# Bias_Regulators_1.net
KiCad netlist of a schematic drawn in Altium Designer
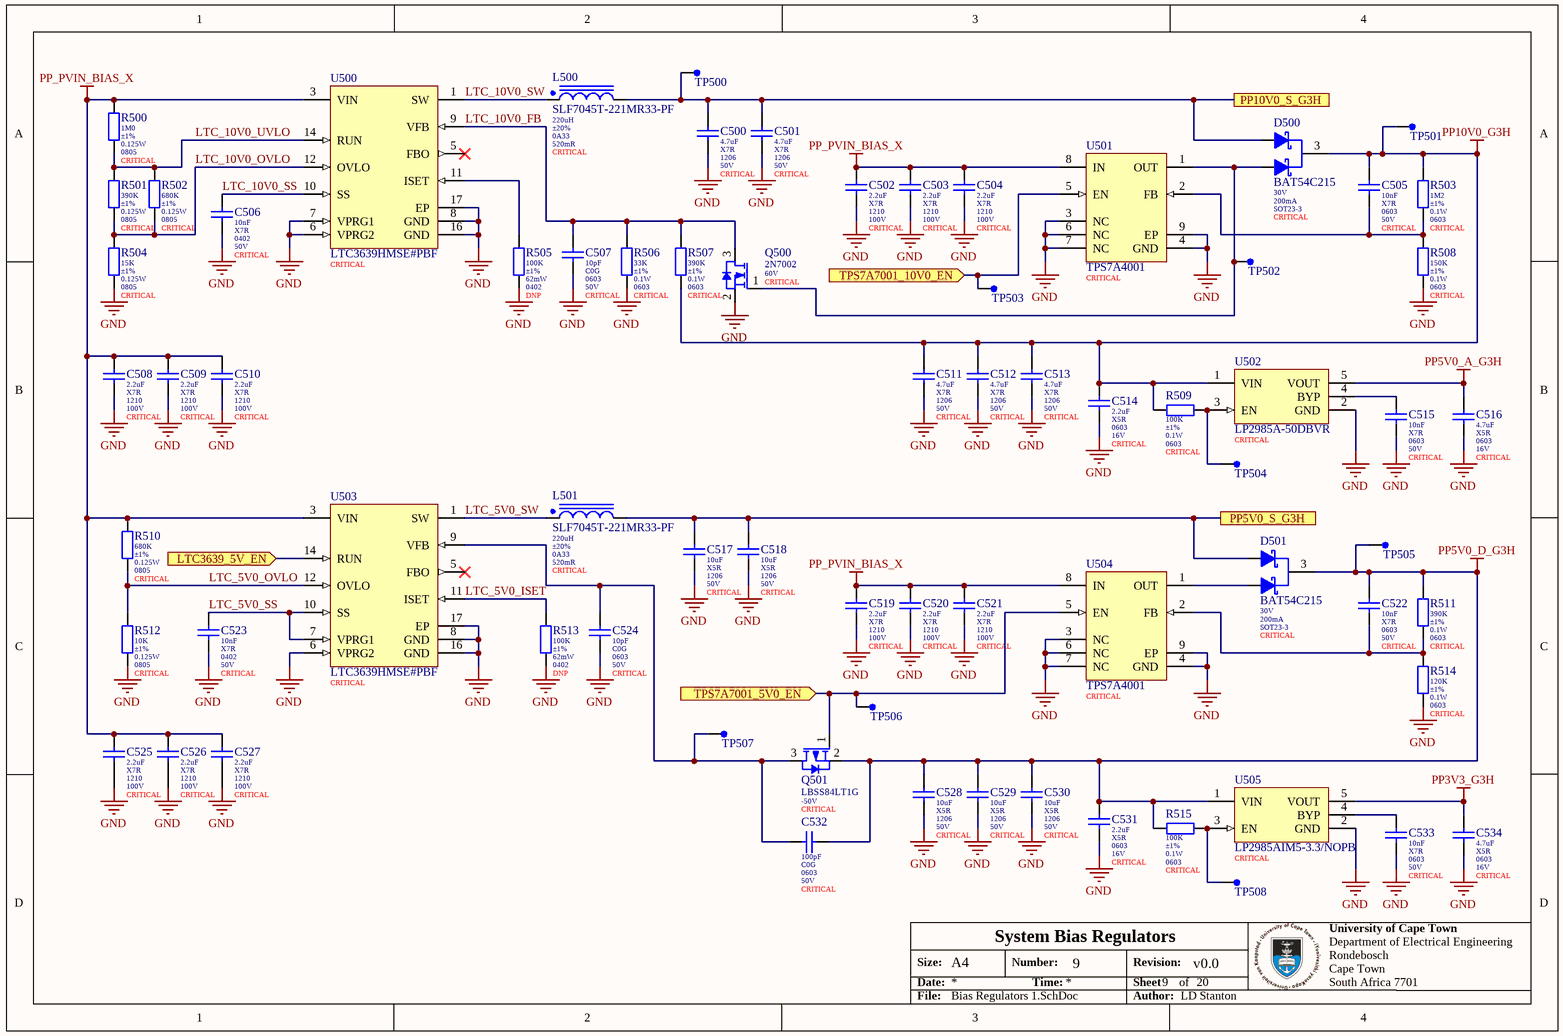
[diagram p0: Bias Regulators 1.SchDoc]

(export (version "E")
  (design (tool "Eeschema 10.0.6"))
  (components
    (comp (ref "C500")
      (value "4.7uF")
      (footprint "1206_125 (Guandong) B")
      (description "MLCC 4.7uF 1206 50V X7R ±10%")
      (fields
        (field (name "DIELECTRIC") "X7R")
        (field (name "PACKAGE") "1206")
        (field (name "VOLTAGE") "50V")
        (field (name "POPULATE") "CRITICAL")
        (field (name "TOLERANCE") "±15%")
        (field (name "MANUFACTURER") "Guandong")
      )
      (libsource (lib "University of Cape Town") (part "Symbol"))
    )
    (comp (ref "C501")
      (value "4.7uF")
      (footprint "1206_125 (Guandong) B")
      (description "MLCC 4.7uF 1206 50V X7R ±10%")
      (fields
        (field (name "DIELECTRIC") "X7R")
        (field (name "PACKAGE") "1206")
        (field (name "VOLTAGE") "50V")
        (field (name "POPULATE") "CRITICAL")
        (field (name "TOLERANCE") "±15%")
        (field (name "MANUFACTURER") "Guandong")
      )
      (libsource (lib "University of Cape Town") (part "Symbol"))
    )
    (comp (ref "C502")
      (value "2.2uF")
      (footprint "1212_250_J (Samsumg) B")
      (description "MLCC 2.2uF 1210 100V X7R ±10%")
      (fields
        (field (name "DIELECTRIC") "X7R")
        (field (name "PACKAGE") "1210")
        (field (name "VOLTAGE") "100V")
        (field (name "POPULATE") "CRITICAL")
        (field (name "LCSC PART NUMBER") "C55151")
        (field (name "TOLERANCE") "±10%")
      )
      (libsource (lib "University of Cape Town") (part "Symbol"))
    )
    (comp (ref "C503")
      (value "2.2uF")
      (footprint "1212_250_J (Samsumg) B")
      (description "MLCC 2.2uF 1210 100V X7R ±10%")
      (fields
        (field (name "DIELECTRIC") "X7R")
        (field (name "PACKAGE") "1210")
        (field (name "VOLTAGE") "100V")
        (field (name "POPULATE") "CRITICAL")
        (field (name "LCSC PART NUMBER") "C55151")
        (field (name "TOLERANCE") "±10%")
      )
      (libsource (lib "University of Cape Town") (part "Symbol"))
    )
    (comp (ref "C504")
      (value "2.2uF")
      (footprint "1212_250_J (Samsumg) B")
      (description "MLCC 2.2uF 1210 100V X7R ±10%")
      (fields
        (field (name "DIELECTRIC") "X7R")
        (field (name "PACKAGE") "1210")
        (field (name "VOLTAGE") "100V")
        (field (name "POPULATE") "CRITICAL")
        (field (name "LCSC PART NUMBER") "C55151")
        (field (name "TOLERANCE") "±10%")
      )
      (libsource (lib "University of Cape Town") (part "Symbol"))
    )
    (comp (ref "C505")
      (value "10nF")
      (footprint "0603_080 (Guandong) B")
      (description "MLCC 10nF 0603 50V X7R ±10%")
      (fields
        (field (name "DIELECTRIC") "X7R")
        (field (name "PACKAGE") "0603")
        (field (name "VOLTAGE") "50V")
        (field (name "POPULATE") "CRITICAL")
        (field (name "LCSC PART NUMBER") "C57112")
        (field (name "MANUFACTURER") "Guandong")
      )
      (libsource (lib "University of Cape Town") (part "Symbol"))
    )
    (comp (ref "C506")
      (value "10nF")
      (footprint "0402_050_5 (Samsumg) B")
      (description "MLCC 10nF 0402 50V X7R ±10%")
      (fields
        (field (name "DIELECTRIC") "X7R")
        (field (name "PACKAGE") "0402")
        (field (name "VOLTAGE") "50V")
        (field (name "POPULATE") "CRITICAL")
        (field (name "TOLERANCE") "±10%")
        (field (name "LCSC PART NUMBER") "C15195")
      )
      (libsource (lib "University of Cape Town") (part "Symbol"))
    )
    (comp (ref "C507")
      (value "10pF")
      (footprint "0603_080_8 (Samsung) B")
      (description "MLCC 10pF 0603 C0G ±0.1pF")
      (fields
        (field (name "DIELECTRIC") "C0G")
        (field (name "PACKAGE") "0603")
        (field (name "VOLTAGE") "50V")
        (field (name "POPULATE") "CRITICAL")
        (field (name "TOLERANCE") "±0.1pF")
        (field (name "LCSC PART NUMBER") "C1634")
      )
      (libsource (lib "University of Cape Town") (part "Symbol"))
    )
    (comp (ref "C508")
      (value "2.2uF")
      (footprint "1212_250_J (Samsumg) B")
      (description "MLCC 2.2uF 1210 100V X7R ±10%")
      (fields
        (field (name "DIELECTRIC") "X7R")
        (field (name "PACKAGE") "1210")
        (field (name "VOLTAGE") "100V")
        (field (name "POPULATE") "CRITICAL")
        (field (name "LCSC PART NUMBER") "C55151")
        (field (name "TOLERANCE") "±10%")
      )
      (libsource (lib "University of Cape Town") (part "Symbol"))
    )
    (comp (ref "C509")
      (value "2.2uF")
      (footprint "1212_250_J (Samsumg) B")
      (description "MLCC 2.2uF 1210 100V X7R ±10%")
      (fields
        (field (name "DIELECTRIC") "X7R")
        (field (name "PACKAGE") "1210")
        (field (name "VOLTAGE") "100V")
        (field (name "POPULATE") "CRITICAL")
        (field (name "LCSC PART NUMBER") "C55151")
        (field (name "TOLERANCE") "±10%")
      )
      (libsource (lib "University of Cape Town") (part "Symbol"))
    )
    (comp (ref "C510")
      (value "2.2uF")
      (footprint "1212_250_J (Samsumg) B")
      (description "MLCC 2.2uF 1210 100V X7R ±10%")
      (fields
        (field (name "DIELECTRIC") "X7R")
        (field (name "PACKAGE") "1210")
        (field (name "VOLTAGE") "100V")
        (field (name "POPULATE") "CRITICAL")
        (field (name "LCSC PART NUMBER") "C55151")
        (field (name "TOLERANCE") "±10%")
      )
      (libsource (lib "University of Cape Town") (part "Symbol"))
    )
    (comp (ref "C511")
      (value "4.7uF")
      (footprint "1206_125 (Guandong) B")
      (description "MLCC 4.7uF 1206 50V X7R ±10%")
      (fields
        (field (name "DIELECTRIC") "X7R")
        (field (name "PACKAGE") "1206")
        (field (name "VOLTAGE") "50V")
        (field (name "POPULATE") "CRITICAL")
        (field (name "TOLERANCE") "±15%")
        (field (name "MANUFACTURER") "Guandong")
      )
      (libsource (lib "University of Cape Town") (part "Symbol"))
    )
    (comp (ref "C512")
      (value "4.7uF")
      (footprint "1206_125 (Guandong) B")
      (description "MLCC 4.7uF 1206 50V X7R ±10%")
      (fields
        (field (name "DIELECTRIC") "X7R")
        (field (name "PACKAGE") "1206")
        (field (name "VOLTAGE") "50V")
        (field (name "POPULATE") "CRITICAL")
        (field (name "TOLERANCE") "±15%")
        (field (name "MANUFACTURER") "Guandong")
      )
      (libsource (lib "University of Cape Town") (part "Symbol"))
    )
    (comp (ref "C513")
      (value "4.7uF")
      (footprint "1206_125 (Guandong) B")
      (description "MLCC 4.7uF 1206 50V X7R ±10%")
      (fields
        (field (name "DIELECTRIC") "X7R")
        (field (name "PACKAGE") "1206")
        (field (name "VOLTAGE") "50V")
        (field (name "POPULATE") "CRITICAL")
        (field (name "TOLERANCE") "±15%")
        (field (name "MANUFACTURER") "Guandong")
      )
      (libsource (lib "University of Cape Town") (part "Symbol"))
    )
    (comp (ref "C514")
      (value "2.2uF")
      (footprint "0603_080_8 (Samsung) B")
      (description "MLCC 2.2uF 0603 16V X5R ±10%")
      (fields
        (field (name "DIELECTRIC") "X5R")
        (field (name "PACKAGE") "0603")
        (field (name "VOLTAGE") "16V")
        (field (name "POPULATE") "CRITICAL")
        (field (name "TOLERANCE") "±10%")
        (field (name "LCSC PART NUMBER") "C23630")
      )
      (libsource (lib "University of Cape Town") (part "Symbol"))
    )
    (comp (ref "C515")
      (value "10nF")
      (footprint "0603_080 (Guandong) B")
      (description "MLCC 10nF 0603 50V X7R ±10%")
      (fields
        (field (name "DIELECTRIC") "X7R")
        (field (name "PACKAGE") "0603")
        (field (name "VOLTAGE") "50V")
        (field (name "POPULATE") "CRITICAL")
        (field (name "LCSC PART NUMBER") "C57112")
        (field (name "MANUFACTURER") "Guandong")
      )
      (libsource (lib "University of Cape Town") (part "Symbol"))
    )
    (comp (ref "C516")
      (value "4.7uF")
      (footprint "0603_080_8 (Samsung) B")
      (description "MLCC 4.7uF 0603 16V X5R ±10%")
      (fields
        (field (name "DIELECTRIC") "X5R")
        (field (name "PACKAGE") "0603")
        (field (name "VOLTAGE") "16V")
        (field (name "POPULATE") "CRITICAL")
        (field (name "LCSC PART NUMBER") "C19666")
        (field (name "TOLERANCE") "±10%")
      )
      (libsource (lib "University of Cape Town") (part "Symbol"))
    )
    (comp (ref "C517")
      (value "10uF")
      (footprint "1206_160_H (Samsumg) B")
      (description "MLCC 10uF 1206 50V X5R ±10%")
      (fields
        (field (name "DIELECTRIC") "X5R")
        (field (name "PACKAGE") "1206")
        (field (name "VOLTAGE") "50V")
        (field (name "POPULATE") "CRITICAL")
        (field (name "LCSC PART NUMBER") "C13585")
        (field (name "MANUFACTURER") "Samsung")
      )
      (libsource (lib "University of Cape Town") (part "Symbol"))
    )
    (comp (ref "C518")
      (value "10uF")
      (footprint "1206_160_H (Samsumg) B")
      (description "MLCC 10uF 1206 50V X5R ±10%")
      (fields
        (field (name "DIELECTRIC") "X5R")
        (field (name "PACKAGE") "1206")
        (field (name "VOLTAGE") "50V")
        (field (name "POPULATE") "CRITICAL")
        (field (name "LCSC PART NUMBER") "C13585")
        (field (name "MANUFACTURER") "Samsung")
      )
      (libsource (lib "University of Cape Town") (part "Symbol"))
    )
    (comp (ref "C519")
      (value "2.2uF")
      (footprint "1212_250_J (Samsumg) B")
      (description "MLCC 2.2uF 1210 100V X7R ±10%")
      (fields
        (field (name "DIELECTRIC") "X7R")
        (field (name "PACKAGE") "1210")
        (field (name "VOLTAGE") "100V")
        (field (name "POPULATE") "CRITICAL")
        (field (name "LCSC PART NUMBER") "C55151")
        (field (name "TOLERANCE") "±10%")
      )
      (libsource (lib "University of Cape Town") (part "Symbol"))
    )
    (comp (ref "C520")
      (value "2.2uF")
      (footprint "1212_250_J (Samsumg) B")
      (description "MLCC 2.2uF 1210 100V X7R ±10%")
      (fields
        (field (name "DIELECTRIC") "X7R")
        (field (name "PACKAGE") "1210")
        (field (name "VOLTAGE") "100V")
        (field (name "POPULATE") "CRITICAL")
        (field (name "LCSC PART NUMBER") "C55151")
        (field (name "TOLERANCE") "±10%")
      )
      (libsource (lib "University of Cape Town") (part "Symbol"))
    )
    (comp (ref "C521")
      (value "2.2uF")
      (footprint "1212_250_J (Samsumg) B")
      (description "MLCC 2.2uF 1210 100V X7R ±10%")
      (fields
        (field (name "DIELECTRIC") "X7R")
        (field (name "PACKAGE") "1210")
        (field (name "VOLTAGE") "100V")
        (field (name "POPULATE") "CRITICAL")
        (field (name "LCSC PART NUMBER") "C55151")
        (field (name "TOLERANCE") "±10%")
      )
      (libsource (lib "University of Cape Town") (part "Symbol"))
    )
    (comp (ref "C522")
      (value "10nF")
      (footprint "0603_080 (Guandong) B")
      (description "MLCC 10nF 0603 50V X7R ±10%")
      (fields
        (field (name "DIELECTRIC") "X7R")
        (field (name "PACKAGE") "0603")
        (field (name "VOLTAGE") "50V")
        (field (name "POPULATE") "CRITICAL")
        (field (name "LCSC PART NUMBER") "C57112")
        (field (name "MANUFACTURER") "Guandong")
      )
      (libsource (lib "University of Cape Town") (part "Symbol"))
    )
    (comp (ref "C523")
      (value "10nF")
      (footprint "0402_050_5 (Samsumg) B")
      (description "MLCC 10nF 0402 50V X7R ±10%")
      (fields
        (field (name "DIELECTRIC") "X7R")
        (field (name "PACKAGE") "0402")
        (field (name "VOLTAGE") "50V")
        (field (name "POPULATE") "CRITICAL")
        (field (name "TOLERANCE") "±10%")
        (field (name "LCSC PART NUMBER") "C15195")
      )
      (libsource (lib "University of Cape Town") (part "Symbol"))
    )
    (comp (ref "C524")
      (value "10pF")
      (footprint "0603_080_8 (Samsung) B")
      (description "MLCC 10pF 0603 C0G ±0.1pF")
      (fields
        (field (name "DIELECTRIC") "C0G")
        (field (name "PACKAGE") "0603")
        (field (name "VOLTAGE") "50V")
        (field (name "POPULATE") "CRITICAL")
        (field (name "LCSC PART NUMBER") "C1634")
        (field (name "MANUFACTURER") "Samsung")
      )
      (libsource (lib "University of Cape Town") (part "Symbol"))
    )
    (comp (ref "C525")
      (value "2.2uF")
      (footprint "1212_250_J (Samsumg) B")
      (description "MLCC 2.2uF 1210 100V X7R ±10%")
      (fields
        (field (name "DIELECTRIC") "X7R")
        (field (name "PACKAGE") "1210")
        (field (name "VOLTAGE") "100V")
        (field (name "POPULATE") "CRITICAL")
        (field (name "LCSC PART NUMBER") "C55151")
        (field (name "TOLERANCE") "±10%")
      )
      (libsource (lib "University of Cape Town") (part "Symbol"))
    )
    (comp (ref "C526")
      (value "2.2uF")
      (footprint "1212_250_J (Samsumg) B")
      (description "MLCC 2.2uF 1210 100V X7R ±10%")
      (fields
        (field (name "DIELECTRIC") "X7R")
        (field (name "PACKAGE") "1210")
        (field (name "VOLTAGE") "100V")
        (field (name "POPULATE") "CRITICAL")
        (field (name "LCSC PART NUMBER") "C55151")
        (field (name "TOLERANCE") "±10%")
      )
      (libsource (lib "University of Cape Town") (part "Symbol"))
    )
    (comp (ref "C527")
      (value "2.2uF")
      (footprint "1212_250_J (Samsumg) B")
      (description "MLCC 2.2uF 1210 100V X7R ±10%")
      (fields
        (field (name "DIELECTRIC") "X7R")
        (field (name "PACKAGE") "1210")
        (field (name "VOLTAGE") "100V")
        (field (name "POPULATE") "CRITICAL")
        (field (name "LCSC PART NUMBER") "C55151")
        (field (name "TOLERANCE") "±10%")
      )
      (libsource (lib "University of Cape Town") (part "Symbol"))
    )
    (comp (ref "C528")
      (value "10uF")
      (footprint "1206_160_H (Samsumg) B")
      (description "MLCC 10uF 1206 50V X5R ±10%")
      (fields
        (field (name "DIELECTRIC") "X5R")
        (field (name "PACKAGE") "1206")
        (field (name "VOLTAGE") "50V")
        (field (name "POPULATE") "CRITICAL")
        (field (name "LCSC PART NUMBER") "C13585")
        (field (name "MANUFACTURER") "Samsung")
      )
      (libsource (lib "University of Cape Town") (part "Symbol"))
    )
    (comp (ref "C529")
      (value "10uF")
      (footprint "1206_160_H (Samsumg) B")
      (description "MLCC 10uF 1206 50V X5R ±10%")
      (fields
        (field (name "DIELECTRIC") "X5R")
        (field (name "PACKAGE") "1206")
        (field (name "VOLTAGE") "50V")
        (field (name "POPULATE") "CRITICAL")
        (field (name "LCSC PART NUMBER") "C13585")
        (field (name "MANUFACTURER") "Samsung")
      )
      (libsource (lib "University of Cape Town") (part "Symbol"))
    )
    (comp (ref "C530")
      (value "10uF")
      (footprint "1206_160_H (Samsumg) B")
      (description "MLCC 10uF 1206 50V X5R ±10%")
      (fields
        (field (name "DIELECTRIC") "X5R")
        (field (name "PACKAGE") "1206")
        (field (name "VOLTAGE") "50V")
        (field (name "POPULATE") "CRITICAL")
        (field (name "LCSC PART NUMBER") "C13585")
        (field (name "MANUFACTURER") "Samsung")
      )
      (libsource (lib "University of Cape Town") (part "Symbol"))
    )
    (comp (ref "C531")
      (value "2.2uF")
      (footprint "0603_080_8 (Samsung) B")
      (description "MLCC 2.2uF 0603 16V X5R ±10%")
      (fields
        (field (name "DIELECTRIC") "X5R")
        (field (name "PACKAGE") "0603")
        (field (name "VOLTAGE") "16V")
        (field (name "POPULATE") "CRITICAL")
        (field (name "TOLERANCE") "±10%")
        (field (name "LCSC PART NUMBER") "C23630")
      )
      (libsource (lib "University of Cape Town") (part "Symbol"))
    )
    (comp (ref "C532")
      (value "100pF")
      (footprint "0603_080_8 (Samsung) B")
      (description "MLCC 100pF 0603 50V C0G ±0.1pF")
      (fields
        (field (name "DIELECTRIC") "C0G")
        (field (name "PACKAGE") "0603")
        (field (name "VOLTAGE") "50V")
        (field (name "POPULATE") "CRITICAL")
        (field (name "LCSC PART NUMBER") "C14858")
        (field (name "MANUFACTURER") "Samsung")
      )
      (libsource (lib "University of Cape Town") (part "Symbol"))
    )
    (comp (ref "C533")
      (value "10nF")
      (footprint "0603_080 (Guandong) B")
      (description "MLCC 10nF 0603 50V X7R ±10%")
      (fields
        (field (name "DIELECTRIC") "X7R")
        (field (name "PACKAGE") "0603")
        (field (name "VOLTAGE") "50V")
        (field (name "POPULATE") "CRITICAL")
        (field (name "LCSC PART NUMBER") "C57112")
        (field (name "MANUFACTURER") "Guandong")
      )
      (libsource (lib "University of Cape Town") (part "Symbol"))
    )
    (comp (ref "C534")
      (value "4.7uF")
      (footprint "0603_080_8 (Samsung) B")
      (description "MLCC 4.7uF 0603 16V X5R ±10%")
      (fields
        (field (name "DIELECTRIC") "X5R")
        (field (name "PACKAGE") "0603")
        (field (name "VOLTAGE") "16V")
        (field (name "POPULATE") "CRITICAL")
        (field (name "LCSC PART NUMBER") "C19666")
        (field (name "TOLERANCE") "±10%")
      )
      (libsource (lib "University of Cape Town") (part "Symbol"))
    )
    (comp (ref "D500")
      (value "BAT54C215")
      (footprint "SOT-23-3 (BAT54C215) A")
      (description "Schottky Barrier Diode Common Cathode 30V 200mA")
      (fields
        (field (name "REVERSE VOLTAGE") "30V")
        (field (name "FORWARD CURRENT") "200mA")
        (field (name "PACKAGE") "SOT23-3")
        (field (name "PLACEMENT") "CRITICAL")
        (field (name "LCSC PART NUMBER") "C37704")
        (field (name "MANUFACTURER") "NXP")
      )
      (libsource (lib "University of Cape Town") (part "BAT54"))
    )
    (comp (ref "D501")
      (value "BAT54C215")
      (footprint "SOT-23-3 (BAT54C215) A")
      (description "Schottky Barrier Diode Common Cathode 30V 200mA")
      (fields
        (field (name "REVERSE VOLTAGE") "30V")
        (field (name "FORWARD CURRENT") "200mA")
        (field (name "PACKAGE") "SOT23-3")
        (field (name "PLACEMENT") "CRITICAL")
        (field (name "LCSC PART NUMBER") "C37704")
        (field (name "MANUFACTURER") "NXP")
      )
      (libsource (lib "University of Cape Town") (part "BAT54"))
    )
    (comp (ref "L500")
      (value "SLF7045T-221MR33-PF")
      (footprint "SLF7045 B")
      (description "Inductor 220uH ±20% 0A65 470mR Wirewound Shielded")
      (fields
        (field (name "ALTIUM_VALUE") "220uH")
        (field (name "TOLERANCE") "±20%")
        (field (name "RATED CURRENT") "0A33")
        (field (name "DC RESISTANCE") "520mR")
        (field (name "POPULATE") "CRITICAL")
        (field (name "MANUFACTURER") "TDK")
        (field (name "LCSC PART NUMBER") "C24679")
      )
      (libsource (lib "University of Cape Town") (part "Inductor Core Polarised"))
    )
    (comp (ref "L501")
      (value "SLF7045T-221MR33-PF")
      (footprint "SLF7045 B")
      (description "Inductor 220uH ±20% 0A65 470mR Wirewound Shielded")
      (fields
        (field (name "ALTIUM_VALUE") "220uH")
        (field (name "TOLERANCE") "±20%")
        (field (name "RATED CURRENT") "0A33")
        (field (name "DC RESISTANCE") "520mR")
        (field (name "POPULATE") "CRITICAL")
        (field (name "MANUFACTURER") "TDK")
        (field (name "LCSC PART NUMBER") "C24679")
      )
      (libsource (lib "University of Cape Town") (part "Inductor Core Polarised"))
    )
    (comp (ref "Q500")
      (value "2N7002")
      (footprint "SOT-23-3 (2N7002) B")
      (description "Small Signal MOSFET, 500 mA, 60 V, N-Channel, Enhancement, JCET SOT-23-3")
      (fields
        (field (name "MAXIMUM DRAIN SOURCE VOLTAGE") "60V")
        (field (name "PLACEMENT") "CRITICAL")
        (field (name "POWER") "0.225W")
        (field (name "MANUFACTURER") "JCET")
      )
      (libsource (lib "University of Cape Town") (part "N Channel Transistor SOT-23-3"))
    )
    (comp (ref "Q501")
      (value "LBSS84LT1G")
      (footprint "SOT-23-3 (LBSS84) B")
      (description "Small Signal MOSFET, 130 mA, 50 V, P-Channel, Enhancement, LRC SOT-23-3")
      (fields
        (field (name "MAXIMUM DRAIN SOURCE VOLTAGE") "-50V")
        (field (name "PLACEMENT") "CRITICAL")
        (field (name "LCSC PART NUMBER") "C8492")
        (field (name "MANUFACTURER") "Leshan Radio Company")
      )
      (libsource (lib "University of Cape Town") (part "P Channel MOSFET SOT-23-3"))
    )
    (comp (ref "R500")
      (value "1M0")
      (footprint "0805 (Uniroyal) B")
      (description "Resistor 1M0 0805 ±1% Thick Film Uniroyal")
      (fields
        (field (name "TOLERANCE") "±1%")
        (field (name "POWER") "0.125W")
        (field (name "PACKAGE") "0805")
        (field (name "POPULATE") "CRITICAL")
        (field (name "LCSC PART NUMBER") "C17514")
        (field (name "MANUFACTURER") "Uniroyal")
      )
      (libsource (lib "University of Cape Town") (part "Chip Resistor"))
    )
    (comp (ref "R501")
      (value "390K")
      (footprint "0805 (Uniroyal) B")
      (description "Resistor 390K 0805 ±1% Thick Film Uniroyal")
      (fields
        (field (name "TOLERANCE") "±1%")
        (field (name "POWER") "0.125W")
        (field (name "PACKAGE") "0805")
        (field (name "POPULATE") "CRITICAL")
        (field (name "LCSC PART NUMBER") "C17656")
        (field (name "MANUFACTURER") "Uniroyal")
      )
      (libsource (lib "University of Cape Town") (part "Chip Resistor"))
    )
    (comp (ref "R502")
      (value "680K")
      (footprint "0805 (Uniroyal) B")
      (description "Resistor 680K 0805 ±1% Thick Film Uniroyal")
      (fields
        (field (name "TOLERANCE") "±1%")
        (field (name "POWER") "0.125W")
        (field (name "PACKAGE") "0805")
        (field (name "POPULATE") "CRITICAL")
        (field (name "LCSC PART NUMBER") "C17797")
        (field (name "MANUFACTURER") "Uniroyal")
      )
      (libsource (lib "University of Cape Town") (part "Chip Resistor"))
    )
    (comp (ref "R503")
      (value "1M2")
      (footprint "0603 (Uniroyal) B")
      (description "Resistor 1M2 0603 ±1% Thick Film Uniroyal")
      (fields
        (field (name "TOLERANCE") "±1%")
        (field (name "POWER") "0.1W")
        (field (name "PACKAGE") "0603")
        (field (name "POPULATE") "CRITICAL")
        (field (name "MANUFACTURER") "Uniroyal")
        (field (name "LCSC PART NUMBER") "C13315")
      )
      (libsource (lib "University of Cape Town") (part "Chip Resistor"))
    )
    (comp (ref "R504")
      (value "15K")
      (footprint "0805 (Uniroyal) B")
      (description "Resistor 15K 0805 ±1% Thick Film Uniroyal")
      (fields
        (field (name "TOLERANCE") "±1%")
        (field (name "POWER") "0.125W")
        (field (name "PACKAGE") "0805")
        (field (name "POPULATE") "CRITICAL")
        (field (name "MANUFACTURER") "Uniroyal")
        (field (name "LCSC PART NUMBER") "C17475")
      )
      (libsource (lib "University of Cape Town") (part "Chip Resistor"))
    )
    (comp (ref "R505")
      (value "100K")
      (footprint "0402 (Uniroyal) B")
      (description "Resistor 100K 0402 ±1% Thick Film Uniroyal")
      (fields
        (field (name "TOLERANCE") "±1%")
        (field (name "POWER") "62mW")
        (field (name "PACKAGE") "0402")
        (field (name "POPULATE") "DNP")
        (field (name "LCSC PART NUMBER") "C25741")
        (field (name "MANUFACTURER") "Uniroyal")
      )
      (libsource (lib "University of Cape Town") (part "Chip Resistor"))
    )
    (comp (ref "R506")
      (value "33K")
      (footprint "0603 (Uniroyal) B")
      (description "Resistor 33K 0603 ±1% Thick Film Uniroyal")
      (fields
        (field (name "TOLERANCE") "±1%")
        (field (name "POWER") "0.1W")
        (field (name "PACKAGE") "0603")
        (field (name "POPULATE") "CRITICAL")
        (field (name "LCSC PART NUMBER") "C4216")
        (field (name "MANUFACTURER") "Uniroyal")
      )
      (libsource (lib "University of Cape Town") (part "Chip Resistor"))
    )
    (comp (ref "R507")
      (value "390K")
      (footprint "0603 (Uniroyal) B")
      (description "Resistor 390K 0603 ±1% Thick Film Uniroyal")
      (fields
        (field (name "TOLERANCE") "±1%")
        (field (name "POWER") "0.1W")
        (field (name "PACKAGE") "0603")
        (field (name "POPULATE") "CRITICAL")
        (field (name "MANUFACTURER") "Uniroyal")
        (field (name "LCSC PART NUMBER") "C23150")
      )
      (libsource (lib "University of Cape Town") (part "Chip Resistor"))
    )
    (comp (ref "R508")
      (value "150K")
      (footprint "0603 (Uniroyal) B")
      (description "Resistor 150K 0603 ±1% Thick Film Uniroyal")
      (fields
        (field (name "TOLERANCE") "±1%")
        (field (name "POWER") "0.1W")
        (field (name "PACKAGE") "0603")
        (field (name "POPULATE") "CRITICAL")
        (field (name "MANUFACTURER") "Uniroyal")
        (field (name "LCSC PART NUMBER") "C22807")
      )
      (libsource (lib "University of Cape Town") (part "Chip Resistor"))
    )
    (comp (ref "R509")
      (value "100K")
      (footprint "0603 (Uniroyal) B")
      (description "Resistor 100K 0603 ±1% Thick Film Uniroyal")
      (fields
        (field (name "TOLERANCE") "±1%")
        (field (name "POWER") "0.1W")
        (field (name "PACKAGE") "0603")
        (field (name "POPULATE") "CRITICAL")
        (field (name "MANUFACTURER") "Uniroyal")
        (field (name "LCSC PART NUMBER") "C25803")
      )
      (libsource (lib "University of Cape Town") (part "Chip Resistor"))
    )
    (comp (ref "R510")
      (value "680K")
      (footprint "0805 (Uniroyal) B")
      (description "Resistor 680K 0805 ±1% Thick Film Uniroyal")
      (fields
        (field (name "TOLERANCE") "±1%")
        (field (name "POWER") "0.125W")
        (field (name "PACKAGE") "0805")
        (field (name "POPULATE") "CRITICAL")
        (field (name "MANUFACTURER") "Uniroyal")
        (field (name "LCSC PART NUMBER") "C17797")
      )
      (libsource (lib "University of Cape Town") (part "Chip Resistor"))
    )
    (comp (ref "R511")
      (value "390K")
      (footprint "0603 (Uniroyal) B")
      (description "Resistor 390K 0603 ±1% Thick Film Uniroyal")
      (fields
        (field (name "TOLERANCE") "±1%")
        (field (name "POWER") "0.1W")
        (field (name "PACKAGE") "0603")
        (field (name "POPULATE") "CRITICAL")
        (field (name "LCSC PART NUMBER") "C23150")
        (field (name "MANUFACTURER") "Uniroyal")
      )
      (libsource (lib "University of Cape Town") (part "Chip Resistor"))
    )
    (comp (ref "R512")
      (value "10K")
      (footprint "0805 (Uniroyal) B")
      (description "Resistor 10K 0805 ±1% Thick Film Uniroyal")
      (fields
        (field (name "TOLERANCE") "±1%")
        (field (name "POWER") "0.125W")
        (field (name "PACKAGE") "0805")
        (field (name "POPULATE") "CRITICAL")
        (field (name "MANUFACTURER") "Uniroyal")
        (field (name "LCSC PART NUMBER") "C17414")
      )
      (libsource (lib "University of Cape Town") (part "Chip Resistor"))
    )
    (comp (ref "R513")
      (value "100K")
      (footprint "0402 (Uniroyal) B")
      (description "Resistor 100K 0402 ±1% Thick Film Uniroyal")
      (fields
        (field (name "TOLERANCE") "±1%")
        (field (name "POWER") "62mW")
        (field (name "PACKAGE") "0402")
        (field (name "POPULATE") "DNP")
        (field (name "LCSC PART NUMBER") "C25741")
        (field (name "MANUFACTURER") "Uniroyal")
      )
      (libsource (lib "University of Cape Town") (part "Chip Resistor"))
    )
    (comp (ref "R514")
      (value "120K")
      (footprint "0603 (Uniroyal) B")
      (description "Resistor 120K 0603 ±1% Thick Film Uniroyal")
      (fields
        (field (name "TOLERANCE") "±1%")
        (field (name "POWER") "0.1W")
        (field (name "PACKAGE") "0603")
        (field (name "POPULATE") "CRITICAL")
        (field (name "MANUFACTURER") "Uniroyal")
        (field (name "LCSC PART NUMBER") "C25808")
      )
      (libsource (lib "University of Cape Town") (part "Chip Resistor"))
    )
    (comp (ref "R515")
      (value "100K")
      (footprint "0603 (Uniroyal) B")
      (description "Resistor 100K 0603 ±1% Thick Film Uniroyal")
      (fields
        (field (name "TOLERANCE") "±1%")
        (field (name "POWER") "0.1W")
        (field (name "PACKAGE") "0603")
        (field (name "POPULATE") "CRITICAL")
        (field (name "MANUFACTURER") "Uniroyal")
        (field (name "LCSC PART NUMBER") "C25803")
      )
      (libsource (lib "University of Cape Town") (part "Chip Resistor"))
    )
    (comp (ref "TP500")
      (value "Test Point")
      (footprint "Test Point Pad 1.0mm")
      (description "Test Point Pad")
      (libsource (lib "University of Cape Town") (part "Test Point"))
    )
    (comp (ref "TP501")
      (value "Test Point")
      (footprint "Test Point Pad 1.0mm")
      (description "Test Point Pad")
      (libsource (lib "University of Cape Town") (part "Test Point"))
    )
    (comp (ref "TP502")
      (value "Test Point")
      (footprint "Test Point Pad 1.0mm")
      (description "Test Point Pad")
      (libsource (lib "University of Cape Town") (part "Test Point"))
    )
    (comp (ref "TP503")
      (value "Test Point")
      (footprint "Test Point Pad 1.0mm")
      (description "Test Point Pad")
      (libsource (lib "University of Cape Town") (part "Test Point"))
    )
    (comp (ref "TP504")
      (value "Test Point")
      (footprint "Test Point Pad 1.0mm")
      (description "Test Point Pad")
      (libsource (lib "University of Cape Town") (part "Test Point"))
    )
    (comp (ref "TP505")
      (value "Test Point")
      (footprint "Test Point Pad 1.0mm")
      (description "Test Point Pad")
      (libsource (lib "University of Cape Town") (part "Test Point"))
    )
    (comp (ref "TP506")
      (value "Test Point")
      (footprint "Test Point Pad 1.0mm")
      (description "Test Point Pad")
      (libsource (lib "University of Cape Town") (part "Test Point"))
    )
    (comp (ref "TP507")
      (value "Test Point")
      (footprint "Test Point Pad 1.0mm")
      (description "Test Point Pad")
      (libsource (lib "University of Cape Town") (part "Test Point"))
    )
    (comp (ref "TP508")
      (value "Test Point")
      (footprint "Test Point Pad 1.0mm")
      (description "Test Point Pad")
      (libsource (lib "University of Cape Town") (part "Test Point"))
    )
    (comp (ref "U500")
      (value "LTC3639HMSE#PBF")
      (footprint "LT-MSE-16-V(12)4PR-EDP_N")
      (description "DC-DC Conv 4V to 150V Synchronous Step Down Single-Out 0.8V to 150V 0.1A Automotive 12-Pin MSOP EP")
      (fields (field (name "PLACEMENT") "CRITICAL"))
      (libsource (lib "University of Cape Town") (part "LT-LTC3639-MSE-16"))
    )
    (comp (ref "U501")
      (value "TPS7A4001")
      (footprint "DGN0008B_N")
      (description "Adjustable LDO Voltage Regulator, 7 V to 100 V, 780 mV Drop, 1.161 V to 90 V / 50 mA out, MSOP-8")
      (fields
        (field (name "PLACEMENT") "CRITICAL")
        (field (name "LCSC PART NUMBER") "C55006")
        (field (name "POWER") "1.83W")
      )
      (libsource (lib "University of Cape Town") (part "TPS7A4001"))
    )
    (comp (ref "U502")
      (value "LP2985A-50DBVR")
      (footprint "SOT-23-5 (DBV0005A) B")
      (description "LDO Fixed 5V, 0.15A, 1% Accuracy, Max 16V Input, 65uA Iq, SOT-23-5")
      (fields
        (field (name "PLACEMENT") "CRITICAL")
        (field (name "MANUFACTURER") "Texas Instruments")
        (field (name "LCSC PART NUMBER") "C109382")
      )
      (libsource (lib "University of Cape Town") (part "LP2985"))
    )
    (comp (ref "U503")
      (value "LTC3639HMSE#PBF")
      (footprint "LT-MSE-16-V(12)4PR-EDP_N")
      (description "DC-DC Conv 4V to 150V Synchronous Step Down Single-Out 0.8V to 150V 0.1A Automotive 12-Pin MSOP EP")
      (fields (field (name "PLACEMENT") "CRITICAL"))
      (libsource (lib "University of Cape Town") (part "LT-LTC3639-MSE-16"))
    )
    (comp (ref "U504")
      (value "TPS7A4001")
      (footprint "DGN0008B_N")
      (description "Adjustable LDO Voltage Regulator, 7 V to 100 V, 780 mV Drop, 1.161 V to 90 V / 50 mA out, MSOP-8")
      (fields
        (field (name "PLACEMENT") "CRITICAL")
        (field (name "LCSC PART NUMBER") "C55006")
        (field (name "POWER") "1.83W")
      )
      (libsource (lib "University of Cape Town") (part "TPS7A4001"))
    )
    (comp (ref "U505")
      (value "LP2985AIM5-3.3/NOPB")
      (footprint "SOT-23-5 (DBV0005A) B")
      (description "LDO Fixed 3V3, 0.15A, ±1% Accuracy, Max 16V Input, 65uA Iq, SOT-23-5")
      (fields
        (field (name "PLACEMENT") "CRITICAL")
        (field (name "MANUFACTURER") "Texas Instruments")
        (field (name "LCSC PART NUMBER") "C16085")
      )
      (libsource (lib "University of Cape Town") (part "LP2985"))
    )
  )
  (nets
    (net (code "1") (name "/LTC3639_5V_EN") (class "Default")
      (node (ref "U503") (pin "14") (pinfunction "RUN_14") (pintype "input"))
    )
    (net (code "2") (name "/LTC_5V0_ISET") (class "Default")
      (node (ref "R513") (pin "1") (pinfunction "1_1") (pintype "passive"))
      (node (ref "U503") (pin "11") (pinfunction "ISET_11") (pintype "input"))
    )
    (net (code "3") (name "/LTC_5V0_OVLO") (class "Default")
      (node (ref "R510") (pin "2") (pinfunction "2_2") (pintype "passive"))
      (node (ref "R512") (pin "1") (pinfunction "1_1") (pintype "passive"))
      (node (ref "U503") (pin "12") (pinfunction "OVLO_12") (pintype "input"))
    )
    (net (code "4") (name "/LTC_5V0_SS") (class "Default")
      (node (ref "C523") (pin "1") (pinfunction "1_1") (pintype "passive"))
      (node (ref "U503") (pin "10") (pinfunction "SS_10") (pintype "input"))
      (node (ref "U503") (pin "7") (pinfunction "VPRG1_7") (pintype "input"))
    )
    (net (code "5") (name "/LTC_5V0_SW") (class "Default")
      (node (ref "L501") (pin "1") (pinfunction "1_1") (pintype "passive"))
      (node (ref "U503") (pin "1") (pinfunction "SW_1") (pintype "power_in"))
    )
    (net (code "6") (name "/LTC_10V0_FB") (class "Default")
      (node (ref "C507") (pin "1") (pinfunction "1_1") (pintype "passive"))
      (node (ref "Q500") (pin "3") (pinfunction "D_3") (pintype "passive"))
      (node (ref "R506") (pin "1") (pinfunction "1_1") (pintype "passive"))
      (node (ref "R507") (pin "1") (pinfunction "1_1") (pintype "passive"))
      (node (ref "U500") (pin "9") (pinfunction "VFB_9") (pintype "input"))
    )
    (net (code "7") (name "/LTC_10V0_OVLO") (class "Default")
      (node (ref "R501") (pin "2") (pinfunction "2_2") (pintype "passive"))
      (node (ref "R502") (pin "2") (pinfunction "2_2") (pintype "passive"))
      (node (ref "R504") (pin "1") (pinfunction "1_1") (pintype "passive"))
      (node (ref "U500") (pin "12") (pinfunction "OVLO_12") (pintype "input"))
    )
    (net (code "8") (name "/LTC_10V0_SS") (class "Default")
      (node (ref "C506") (pin "1") (pinfunction "1_1") (pintype "passive"))
      (node (ref "U500") (pin "10") (pinfunction "SS_10") (pintype "input"))
    )
    (net (code "9") (name "/LTC_10V0_SW") (class "Default")
      (node (ref "L500") (pin "1") (pinfunction "1_1") (pintype "passive"))
      (node (ref "U500") (pin "1") (pinfunction "SW_1") (pintype "power_in"))
    )
    (net (code "10") (name "/LTC_10V0_UVLO") (class "Default")
      (node (ref "R500") (pin "2") (pinfunction "2_2") (pintype "passive"))
      (node (ref "R501") (pin "1") (pinfunction "1_1") (pintype "passive"))
      (node (ref "R502") (pin "1") (pinfunction "1_1") (pintype "passive"))
      (node (ref "U500") (pin "14") (pinfunction "RUN_14") (pintype "input"))
    )
    (net (code "11") (name "/PP5V0_S_G3H") (class "Default")
      (node (ref "C517") (pin "1") (pinfunction "1_1") (pintype "passive"))
      (node (ref "C518") (pin "1") (pinfunction "1_1") (pintype "passive"))
      (node (ref "D501") (pin "1") (pinfunction "A1_1") (pintype "passive"))
      (node (ref "L501") (pin "2") (pinfunction "2_2") (pintype "passive"))
    )
    (net (code "12") (name "/PP10V0_S_G3H") (class "Default")
      (node (ref "C500") (pin "1") (pinfunction "1_1") (pintype "passive"))
      (node (ref "C501") (pin "1") (pinfunction "1_1") (pintype "passive"))
      (node (ref "D500") (pin "1") (pinfunction "A1_1") (pintype "passive"))
      (node (ref "L500") (pin "2") (pinfunction "2_2") (pintype "passive"))
      (node (ref "TP500") (pin "1") (pinfunction "1_1") (pintype "passive"))
    )
    (net (code "13") (name "/TPS7A7001_5V0_EN") (class "Default")
      (node (ref "Q501") (pin "1") (pinfunction "G_1") (pintype "passive"))
      (node (ref "TP506") (pin "1") (pinfunction "1_1") (pintype "passive"))
      (node (ref "U504") (pin "5") (pinfunction "EN_5") (pintype "input"))
    )
    (net (code "14") (name "/TPS7A7001_10V0_EN") (class "Default")
      (node (ref "TP503") (pin "1") (pinfunction "1_1") (pintype "passive"))
      (node (ref "U501") (pin "5") (pinfunction "EN_5") (pintype "input"))
    )
    (net (code "15") (name "GND") (class "Default")
      (node (ref "C500") (pin "2") (pinfunction "2_2") (pintype "passive"))
      (node (ref "C501") (pin "2") (pinfunction "2_2") (pintype "passive"))
      (node (ref "C502") (pin "2") (pinfunction "2_2") (pintype "passive"))
      (node (ref "C503") (pin "2") (pinfunction "2_2") (pintype "passive"))
      (node (ref "C504") (pin "2") (pinfunction "2_2") (pintype "passive"))
      (node (ref "C506") (pin "2") (pinfunction "2_2") (pintype "passive"))
      (node (ref "C507") (pin "2") (pinfunction "2_2") (pintype "passive"))
      (node (ref "C508") (pin "2") (pinfunction "2_2") (pintype "passive"))
      (node (ref "C509") (pin "2") (pinfunction "2_2") (pintype "passive"))
      (node (ref "C510") (pin "2") (pinfunction "2_2") (pintype "passive"))
      (node (ref "C511") (pin "2") (pinfunction "2_2") (pintype "passive"))
      (node (ref "C512") (pin "2") (pinfunction "2_2") (pintype "passive"))
      (node (ref "C513") (pin "2") (pinfunction "2_2") (pintype "passive"))
      (node (ref "C514") (pin "2") (pinfunction "2_2") (pintype "passive"))
      (node (ref "C515") (pin "2") (pinfunction "2_2") (pintype "passive"))
      (node (ref "C516") (pin "2") (pinfunction "2_2") (pintype "passive"))
      (node (ref "C517") (pin "2") (pinfunction "2_2") (pintype "passive"))
      (node (ref "C518") (pin "2") (pinfunction "2_2") (pintype "passive"))
      (node (ref "C519") (pin "2") (pinfunction "2_2") (pintype "passive"))
      (node (ref "C520") (pin "2") (pinfunction "2_2") (pintype "passive"))
      (node (ref "C521") (pin "2") (pinfunction "2_2") (pintype "passive"))
      (node (ref "C523") (pin "2") (pinfunction "2_2") (pintype "passive"))
      (node (ref "C524") (pin "2") (pinfunction "2_2") (pintype "passive"))
      (node (ref "C525") (pin "2") (pinfunction "2_2") (pintype "passive"))
      (node (ref "C526") (pin "2") (pinfunction "2_2") (pintype "passive"))
      (node (ref "C527") (pin "2") (pinfunction "2_2") (pintype "passive"))
      (node (ref "C528") (pin "2") (pinfunction "2_2") (pintype "passive"))
      (node (ref "C529") (pin "2") (pinfunction "2_2") (pintype "passive"))
      (node (ref "C530") (pin "2") (pinfunction "2_2") (pintype "passive"))
      (node (ref "C531") (pin "2") (pinfunction "2_2") (pintype "passive"))
      (node (ref "C533") (pin "2") (pinfunction "2_2") (pintype "passive"))
      (node (ref "C534") (pin "2") (pinfunction "2_2") (pintype "passive"))
      (node (ref "Q500") (pin "2") (pinfunction "S_2") (pintype "passive"))
      (node (ref "R504") (pin "2") (pinfunction "2_2") (pintype "passive"))
      (node (ref "R505") (pin "2") (pinfunction "2_2") (pintype "passive"))
      (node (ref "R506") (pin "2") (pinfunction "2_2") (pintype "passive"))
      (node (ref "R508") (pin "2") (pinfunction "2_2") (pintype "passive"))
      (node (ref "R512") (pin "2") (pinfunction "2_2") (pintype "passive"))
      (node (ref "R513") (pin "2") (pinfunction "2_2") (pintype "passive"))
      (node (ref "R514") (pin "2") (pinfunction "2_2") (pintype "passive"))
      (node (ref "U500") (pin "16") (pinfunction "GND_16") (pintype "power_in"))
      (node (ref "U500") (pin "17") (pinfunction "EP_17") (pintype "power_in"))
      (node (ref "U500") (pin "6") (pinfunction "VPRG2_6") (pintype "input"))
      (node (ref "U500") (pin "7") (pinfunction "VPRG1_7") (pintype "input"))
      (node (ref "U500") (pin "8") (pinfunction "GND_8") (pintype "power_in"))
      (node (ref "U501") (pin "3") (pinfunction "NC_3") (pintype "passive"))
      (node (ref "U501") (pin "4") (pinfunction "GND_4") (pintype "power_in"))
      (node (ref "U501") (pin "6") (pinfunction "NC_6") (pintype "passive"))
      (node (ref "U501") (pin "7") (pinfunction "NC_7") (pintype "passive"))
      (node (ref "U501") (pin "9") (pinfunction "EP_9") (pintype "power_in"))
      (node (ref "U502") (pin "2") (pinfunction "GND_2") (pintype "power_in"))
      (node (ref "U503") (pin "16") (pinfunction "GND_16") (pintype "power_in"))
      (node (ref "U503") (pin "17") (pinfunction "EP_17") (pintype "power_in"))
      (node (ref "U503") (pin "6") (pinfunction "VPRG2_6") (pintype "input"))
      (node (ref "U503") (pin "8") (pinfunction "GND_8") (pintype "power_in"))
      (node (ref "U504") (pin "3") (pinfunction "NC_3") (pintype "passive"))
      (node (ref "U504") (pin "4") (pinfunction "GND_4") (pintype "power_in"))
      (node (ref "U504") (pin "6") (pinfunction "NC_6") (pintype "passive"))
      (node (ref "U504") (pin "7") (pinfunction "NC_7") (pintype "passive"))
      (node (ref "U504") (pin "9") (pinfunction "EP_9") (pintype "power_in"))
      (node (ref "U505") (pin "2") (pinfunction "GND_2") (pintype "power_in"))
    )
    (net (code "16") (name "Net-(D500-A2)") (class "Default")
      (node (ref "D500") (pin "2") (pinfunction "A2_2") (pintype "passive"))
      (node (ref "Q500") (pin "1") (pinfunction "G_1") (pintype "passive"))
      (node (ref "TP502") (pin "1") (pinfunction "1_1") (pintype "passive"))
      (node (ref "U501") (pin "1") (pinfunction "OUT_1") (pintype "power_in"))
    )
    (net (code "17") (name "Net-(D501-A2)") (class "Default")
      (node (ref "D501") (pin "2") (pinfunction "A2_2") (pintype "passive"))
      (node (ref "U504") (pin "1") (pinfunction "OUT_1") (pintype "power_in"))
    )
    (net (code "18") (name "Net-(Q501-D)") (class "Default")
      (node (ref "C524") (pin "1") (pinfunction "1_1") (pintype "passive"))
      (node (ref "C532") (pin "1") (pinfunction "1_1") (pintype "passive"))
      (node (ref "Q501") (pin "3") (pinfunction "D_3") (pintype "passive"))
      (node (ref "TP507") (pin "1") (pinfunction "1_1") (pintype "passive"))
      (node (ref "U503") (pin "9") (pinfunction "VFB_9") (pintype "input"))
    )
    (net (code "19") (name "Net-(U500-ISET)") (class "Default")
      (node (ref "R505") (pin "1") (pinfunction "1_1") (pintype "passive"))
      (node (ref "U500") (pin "11") (pinfunction "ISET_11") (pintype "input"))
    )
    (net (code "20") (name "Net-(U501-FB)") (class "Default")
      (node (ref "C505") (pin "2") (pinfunction "2_2") (pintype "passive"))
      (node (ref "R503") (pin "2") (pinfunction "2_2") (pintype "passive"))
      (node (ref "R508") (pin "1") (pinfunction "1_1") (pintype "passive"))
      (node (ref "U501") (pin "2") (pinfunction "FB_2") (pintype "input"))
    )
    (net (code "21") (name "Net-(U502-BYP)") (class "Default")
      (node (ref "C515") (pin "1") (pinfunction "1_1") (pintype "passive"))
      (node (ref "U502") (pin "4") (pinfunction "BYP_4") (pintype "passive"))
    )
    (net (code "22") (name "Net-(U502-EN)") (class "Default")
      (node (ref "R509") (pin "2") (pinfunction "2_2") (pintype "passive"))
      (node (ref "TP504") (pin "1") (pinfunction "1_1") (pintype "passive"))
      (node (ref "U502") (pin "3") (pinfunction "EN_3") (pintype "input"))
    )
    (net (code "23") (name "Net-(U504-FB)") (class "Default")
      (node (ref "C522") (pin "2") (pinfunction "2_2") (pintype "passive"))
      (node (ref "R511") (pin "2") (pinfunction "2_2") (pintype "passive"))
      (node (ref "R514") (pin "1") (pinfunction "1_1") (pintype "passive"))
      (node (ref "U504") (pin "2") (pinfunction "FB_2") (pintype "input"))
    )
    (net (code "24") (name "Net-(U505-BYP)") (class "Default")
      (node (ref "C533") (pin "1") (pinfunction "1_1") (pintype "passive"))
      (node (ref "U505") (pin "4") (pinfunction "BYP_4") (pintype "passive"))
    )
    (net (code "25") (name "Net-(U505-EN)") (class "Default")
      (node (ref "R515") (pin "2") (pinfunction "2_2") (pintype "passive"))
      (node (ref "TP508") (pin "1") (pinfunction "1_1") (pintype "passive"))
      (node (ref "U505") (pin "3") (pinfunction "EN_3") (pintype "input"))
    )
    (net (code "26") (name "PP3V3_G3H") (class "Default")
      (node (ref "C534") (pin "1") (pinfunction "1_1") (pintype "passive"))
      (node (ref "U505") (pin "5") (pinfunction "VOUT_5") (pintype "power_in"))
    )
    (net (code "27") (name "PP5V0_A_G3H") (class "Default")
      (node (ref "C516") (pin "1") (pinfunction "1_1") (pintype "passive"))
      (node (ref "U502") (pin "5") (pinfunction "VOUT_5") (pintype "power_in"))
    )
    (net (code "28") (name "PP5V0_D_G3H") (class "Default")
      (node (ref "C522") (pin "1") (pinfunction "1_1") (pintype "passive"))
      (node (ref "C528") (pin "1") (pinfunction "1_1") (pintype "passive"))
      (node (ref "C529") (pin "1") (pinfunction "1_1") (pintype "passive"))
      (node (ref "C530") (pin "1") (pinfunction "1_1") (pintype "passive"))
      (node (ref "C531") (pin "1") (pinfunction "1_1") (pintype "passive"))
      (node (ref "C532") (pin "2") (pinfunction "2_2") (pintype "passive"))
      (node (ref "D501") (pin "3") (pinfunction "K_3") (pintype "passive"))
      (node (ref "Q501") (pin "2") (pinfunction "S_2") (pintype "passive"))
      (node (ref "R511") (pin "1") (pinfunction "1_1") (pintype "passive"))
      (node (ref "R515") (pin "1") (pinfunction "1_1") (pintype "passive"))
      (node (ref "TP505") (pin "1") (pinfunction "1_1") (pintype "passive"))
      (node (ref "U505") (pin "1") (pinfunction "VIN_1") (pintype "power_in"))
    )
    (net (code "29") (name "PP10V0_G3H") (class "Default")
      (node (ref "C505") (pin "1") (pinfunction "1_1") (pintype "passive"))
      (node (ref "C511") (pin "1") (pinfunction "1_1") (pintype "passive"))
      (node (ref "C512") (pin "1") (pinfunction "1_1") (pintype "passive"))
      (node (ref "C513") (pin "1") (pinfunction "1_1") (pintype "passive"))
      (node (ref "C514") (pin "1") (pinfunction "1_1") (pintype "passive"))
      (node (ref "D500") (pin "3") (pinfunction "K_3") (pintype "passive"))
      (node (ref "R503") (pin "1") (pinfunction "1_1") (pintype "passive"))
      (node (ref "R507") (pin "2") (pinfunction "2_2") (pintype "passive"))
      (node (ref "R509") (pin "1") (pinfunction "1_1") (pintype "passive"))
      (node (ref "TP501") (pin "1") (pinfunction "1_1") (pintype "passive"))
      (node (ref "U502") (pin "1") (pinfunction "VIN_1") (pintype "power_in"))
    )
    (net (code "30") (name "PP_PVIN_BIAS_X") (class "Default")
      (node (ref "C502") (pin "1") (pinfunction "1_1") (pintype "passive"))
      (node (ref "C503") (pin "1") (pinfunction "1_1") (pintype "passive"))
      (node (ref "C504") (pin "1") (pinfunction "1_1") (pintype "passive"))
      (node (ref "C508") (pin "1") (pinfunction "1_1") (pintype "passive"))
      (node (ref "C509") (pin "1") (pinfunction "1_1") (pintype "passive"))
      (node (ref "C510") (pin "1") (pinfunction "1_1") (pintype "passive"))
      (node (ref "C519") (pin "1") (pinfunction "1_1") (pintype "passive"))
      (node (ref "C520") (pin "1") (pinfunction "1_1") (pintype "passive"))
      (node (ref "C521") (pin "1") (pinfunction "1_1") (pintype "passive"))
      (node (ref "C525") (pin "1") (pinfunction "1_1") (pintype "passive"))
      (node (ref "C526") (pin "1") (pinfunction "1_1") (pintype "passive"))
      (node (ref "C527") (pin "1") (pinfunction "1_1") (pintype "passive"))
      (node (ref "R500") (pin "1") (pinfunction "1_1") (pintype "passive"))
      (node (ref "R510") (pin "1") (pinfunction "1_1") (pintype "passive"))
      (node (ref "U500") (pin "3") (pinfunction "VIN_3") (pintype "power_in"))
      (node (ref "U501") (pin "8") (pinfunction "IN_8") (pintype "power_in"))
      (node (ref "U503") (pin "3") (pinfunction "VIN_3") (pintype "power_in"))
      (node (ref "U504") (pin "8") (pinfunction "IN_8") (pintype "power_in"))
    )
    (net (code "31") (name "unconnected-(U500-FBO-Pad5)") (class "Default")
      (node (ref "U500") (pin "5") (pinfunction "FBO_5") (pintype "output+no_connect"))
    )
    (net (code "32") (name "unconnected-(U503-FBO-Pad5)") (class "Default")
      (node (ref "U503") (pin "5") (pinfunction "FBO_5") (pintype "output+no_connect"))
    )
  )
)
